# Motor1.net
KiCad netlist of a schematic drawn in Altium Designer
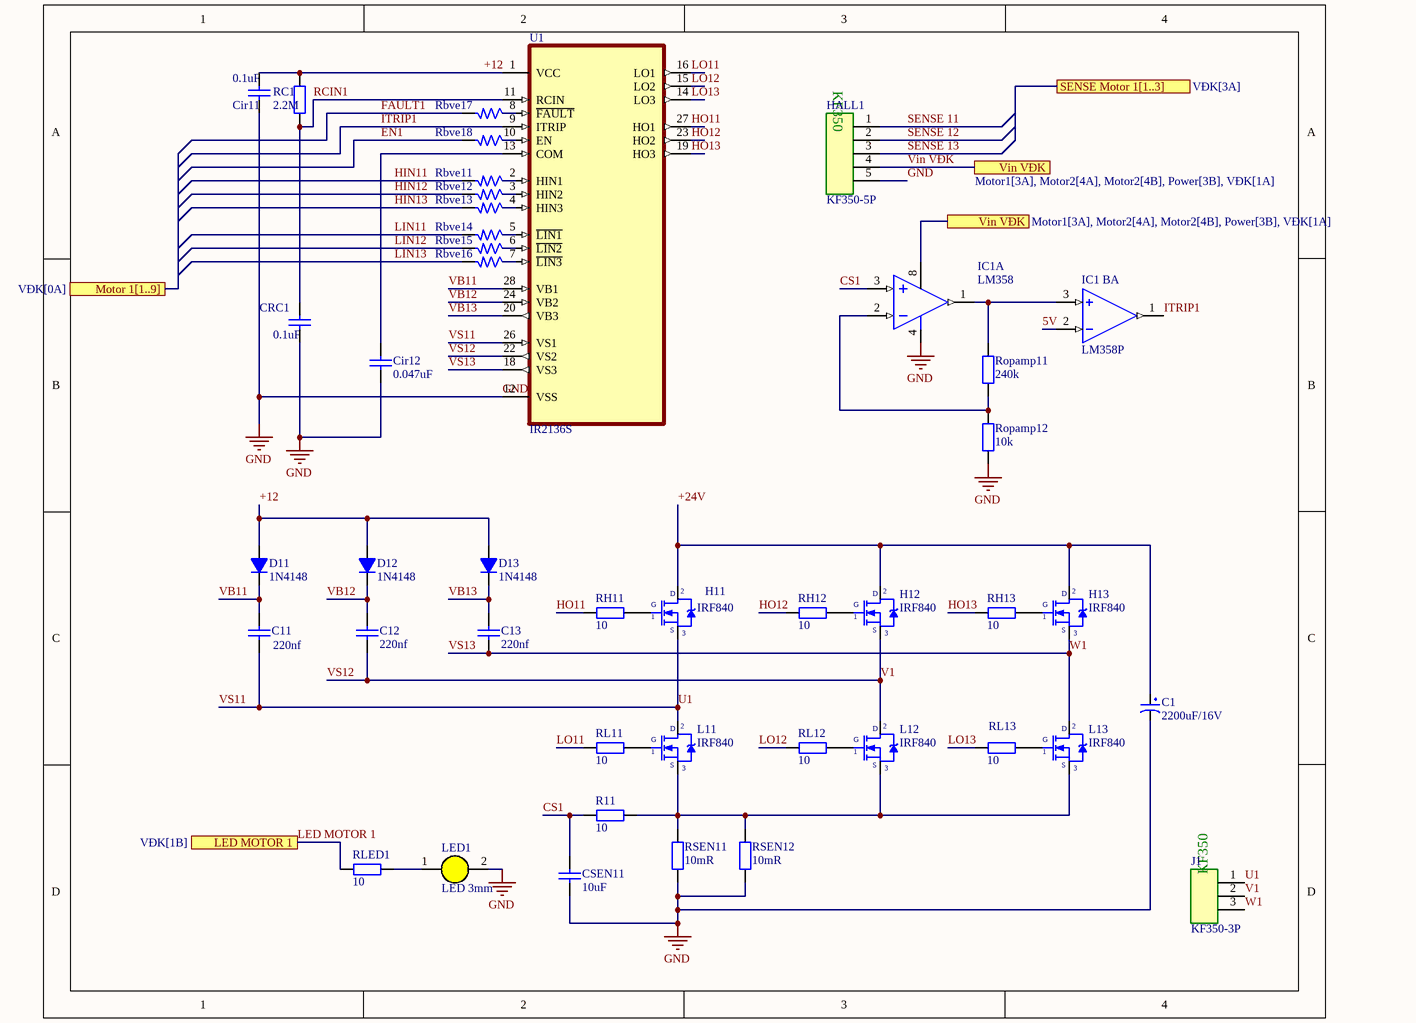
[diagram p0: Motor1.SchDoc]

(export (version "E")
  (design (tool "Eeschema 10.0.6"))
  (components
    (comp (ref "C1")
      (value "2200uF/16V")
      (footprint "CP2/4")
      (description "Cap 2200uF/16V - 1000uF/50V")
      (libsource (lib "SCH_Lib_Devzone") (part "CP5"))
    )
    (comp (ref "C11")
      (value "220nf")
      (footprint "Tu-pico")
      (description "Capacitor")
      (fields (field (name "Comment") "Capacitor Ceramic") (field (name "PUBLISHER") "Altium Limited"))
      (libsource (lib "Devzone_SCHLib") (part "CapCeramic"))
    )
    (comp (ref "C12")
      (value "220nf")
      (footprint "Tu-pico")
      (description "Capacitor")
      (fields (field (name "Comment") "Capacitor Ceramic") (field (name "PUBLISHER") "Altium Limited"))
      (libsource (lib "Devzone_SCHLib") (part "CapCeramic"))
    )
    (comp (ref "C13")
      (value "220nf")
      (footprint "Tu-pico")
      (description "Capacitor")
      (fields (field (name "Comment") "Capacitor Ceramic") (field (name "PUBLISHER") "Altium Limited"))
      (libsource (lib "Devzone_SCHLib") (part "CapCeramic"))
    )
    (comp (ref "Cir11")
      (value "0.1uF")
      (footprint "Tu-pico")
      (description "Capacitor")
      (fields (field (name "Comment") "Capacitor Ceramic") (field (name "PUBLISHER") "Altium Limited"))
      (libsource (lib "Devzone_SCHLib") (part "CapCeramic"))
    )
    (comp (ref "Cir12")
      (value "0.047uF")
      (footprint "Tu-pico")
      (description "Capacitor")
      (fields (field (name "Comment") "Capacitor Ceramic") (field (name "PUBLISHER") "Altium Limited"))
      (libsource (lib "Devzone_SCHLib") (part "CapCeramic"))
    )
    (comp (ref "CRC1")
      (value "0.1uF")
      (footprint "Tu-pico")
      (description "Capacitor")
      (fields (field (name "Comment") "Capacitor Ceramic") (field (name "PUBLISHER") "Altium Limited"))
      (libsource (lib "Devzone_SCHLib") (part "CapCeramic"))
    )
    (comp (ref "CSEN11")
      (value "10uF")
      (footprint "Tu-pico")
      (description "Capacitor")
      (fields (field (name "Comment") "Capacitor Ceramic") (field (name "PUBLISHER") "Altium Limited"))
      (libsource (lib "Devzone_SCHLib") (part "CapCeramic"))
    )
    (comp (ref "D11")
      (value "1N4148")
      (footprint "D0.5A")
      (description "D0.5A")
      (libsource (lib "Devzone_SCHLib") (part "D0.5A"))
    )
    (comp (ref "D12")
      (value "1N4148")
      (footprint "D0.5A")
      (description "D0.5A")
      (libsource (lib "Devzone_SCHLib") (part "D0.5A"))
    )
    (comp (ref "D13")
      (value "1N4148")
      (footprint "D0.5A")
      (description "D0.5A")
      (libsource (lib "Devzone_SCHLib") (part "D0.5A"))
    )
    (comp (ref "H11")
      (value "IRF840")
      (footprint "QTO-220")
      (description "MOSFET N - CHANNEL 500V - 0.75 - 8A - TO-220")
      (libsource (lib "Devzone_SCHLib") (part "IRF840"))
    )
    (comp (ref "H12")
      (value "IRF840")
      (footprint "QTO-220")
      (description "MOSFET N - CHANNEL 500V - 0.75 - 8A - TO-220")
      (libsource (lib "Devzone_SCHLib") (part "IRF840"))
    )
    (comp (ref "H13")
      (value "IRF840")
      (footprint "QTO-220")
      (description "MOSFET N - CHANNEL 500V - 0.75 - 8A - TO-220")
      (libsource (lib "Devzone_SCHLib") (part "IRF840"))
    )
    (comp (ref "HALL1") (value "KF350-5P") (footprint "KF350-5P") (libsource (lib "KF350") (part "KF350-5P")))
    (comp (ref "IC1")
      (value "LM358")
      (footprint "DIP8/W0.3")
      (description "Low-Power Dual Operational Amplifier")
      (libsource (lib "SCH_Lib_Devzone") (part "LM358"))
    )
    (comp (ref "IC1 B")
      (value "LM358P")
      (footprint "DIP794W45P254L959H508Q8")
      (description "Dual, 30-V, 700-kHz operational amplifier")
      (fields (field (name "MF") "Texas Instruments"))
      (libsource (lib "LM358P") (part "LM358P"))
    )
    (comp (ref "J1") (value "KF350-3P") (footprint "KF350-3P") (libsource (lib "KF350") (part "KF350-3P")))
    (comp (ref "L11")
      (value "IRF840")
      (footprint "QTO-220")
      (description "MOSFET N - CHANNEL 500V - 0.75 - 8A - TO-220")
      (libsource (lib "Devzone_SCHLib") (part "IRF840"))
    )
    (comp (ref "L12")
      (value "IRF840")
      (footprint "QTO-220")
      (description "MOSFET N - CHANNEL 500V - 0.75 - 8A - TO-220")
      (libsource (lib "Devzone_SCHLib") (part "IRF840"))
    )
    (comp (ref "L13")
      (value "IRF840")
      (footprint "QTO-220")
      (description "MOSFET N - CHANNEL 500V - 0.75 - 8A - TO-220")
      (libsource (lib "Devzone_SCHLib") (part "IRF840"))
    )
    (comp (ref "LED1")
      (value "LED 3mm")
      (footprint "LED-3MM-YELLOW")
      (description "Cắm")
      (libsource (lib "Altium_Lib_by_KhueNguyenCreator") (part "LED 3mm Vang"))
    )
    (comp (ref "R11")
      (value "10")
      (footprint "R1/4W")
      (description "Resistor 1/4W")
      (libsource (lib "Devzone_SCHLib") (part "R1/4W"))
    )
    (comp (ref "Rbve11")
      (value "1m")
      (footprint "SM-1206")
      (description "Resistor 1/4W")
      (libsource (lib "SCH_Lib_Devzone") (part "R"))
    )
    (comp (ref "Rbve12")
      (value "1m")
      (footprint "SM-1206")
      (description "Resistor 1/4W")
      (libsource (lib "SCH_Lib_Devzone") (part "R"))
    )
    (comp (ref "Rbve13")
      (value "1m")
      (footprint "SM-1206")
      (description "Resistor 1/4W")
      (libsource (lib "SCH_Lib_Devzone") (part "R"))
    )
    (comp (ref "Rbve14")
      (value "1m")
      (footprint "SM-1206")
      (description "Resistor 1/4W")
      (libsource (lib "SCH_Lib_Devzone") (part "R"))
    )
    (comp (ref "Rbve15")
      (value "1m")
      (footprint "SM-1206")
      (description "Resistor 1/4W")
      (libsource (lib "SCH_Lib_Devzone") (part "R"))
    )
    (comp (ref "Rbve16")
      (value "1m")
      (footprint "SM-1206")
      (description "Resistor 1/4W")
      (libsource (lib "SCH_Lib_Devzone") (part "R"))
    )
    (comp (ref "Rbve17")
      (value "1m")
      (footprint "SM-1206")
      (description "Resistor 1/4W")
      (libsource (lib "SCH_Lib_Devzone") (part "R"))
    )
    (comp (ref "Rbve18")
      (value "1m")
      (footprint "SM-1206")
      (description "Resistor 1/4W")
      (libsource (lib "SCH_Lib_Devzone") (part "R"))
    )
    (comp (ref "RC1")
      (value "2.2M")
      (footprint "R1/4W")
      (description "Resistor 1/4W")
      (libsource (lib "Devzone_SCHLib") (part "R1/4W"))
    )
    (comp (ref "RH11")
      (value "10")
      (footprint "R1/4W")
      (description "Resistor 1/4W")
      (libsource (lib "Devzone_SCHLib") (part "R1/4W"))
    )
    (comp (ref "RH12")
      (value "10")
      (footprint "R1/4W")
      (description "Resistor 1/4W")
      (libsource (lib "Devzone_SCHLib") (part "R1/4W"))
    )
    (comp (ref "RH13")
      (value "10")
      (footprint "R1/4W")
      (description "Resistor 1/4W")
      (libsource (lib "Devzone_SCHLib") (part "R1/4W"))
    )
    (comp (ref "RL11")
      (value "10")
      (footprint "R1/4W")
      (description "Resistor 1/4W")
      (libsource (lib "Devzone_SCHLib") (part "R1/4W"))
    )
    (comp (ref "RL12")
      (value "10")
      (footprint "R1/4W")
      (description "Resistor 1/4W")
      (libsource (lib "Devzone_SCHLib") (part "R1/4W"))
    )
    (comp (ref "RL13")
      (value "10")
      (footprint "R1/4W")
      (description "Resistor 1/4W")
      (libsource (lib "Devzone_SCHLib") (part "R1/4W"))
    )
    (comp (ref "RLED1")
      (value "10")
      (footprint "R1/4W")
      (description "Resistor 1/4W")
      (libsource (lib "Devzone_SCHLib") (part "R1/4W"))
    )
    (comp (ref "Ropamp11")
      (value "240k")
      (footprint "R1/4W")
      (description "Resistor 1/4W")
      (libsource (lib "Devzone_SCHLib") (part "R1/4W"))
    )
    (comp (ref "Ropamp12")
      (value "10k")
      (footprint "R1/4W")
      (description "Resistor 1/4W")
      (libsource (lib "Devzone_SCHLib") (part "R1/4W"))
    )
    (comp (ref "RSEN11")
      (value "10mR")
      (footprint "Shunt 10mR 1.2x10x7MM")
      (description "Shunt 10mR 1.2x10x7MM")
      (libsource (lib "SCH_Lib_Devzone") (part "Shunt 10mR 1.2x10x7MM"))
    )
    (comp (ref "RSEN12")
      (value "10mR")
      (footprint "Shunt 10mR 1.2x10x7MM")
      (description "Shunt 10mR 1.2x10x7MM")
      (libsource (lib "SCH_Lib_Devzone") (part "Shunt 10mR 1.2x10x7MM"))
    )
    (comp (ref "U1")
      (value "IR2136S")
      (footprint "SOIC127PX1032X265-28N")
      (description "IC Ä‘iá»u khiá»ƒn ná»­a cáº§u cá»•ng Ä‘áº£o ngÆ°á»£c 28-SOIC")
      (fields (field (name "MF") "Infineon"))
      (libsource (lib "IR2136S") (part "IR2136S"))
    )
  )
  (nets
    (net (code "1") (name "/+12") (class "Default")
      (node (ref "Cir11") (pin "1") (pinfunction "1_1") (pintype "passive"))
      (node (ref "D11") (pin "1") (pinfunction "A_1") (pintype "passive"))
      (node (ref "D12") (pin "1") (pinfunction "A_1") (pintype "passive"))
      (node (ref "D13") (pin "1") (pinfunction "A_1") (pintype "passive"))
      (node (ref "RC1") (pin "2") (pinfunction "2_2") (pintype "passive"))
      (node (ref "U1") (pin "1") (pinfunction "VCC_1") (pintype "power_in"))
    )
    (net (code "2") (name "/+24V") (class "Default")
      (node (ref "C1") (pin "1") (pinfunction "1_1") (pintype "passive"))
      (node (ref "H11") (pin "2") (pinfunction "D_2") (pintype "passive"))
      (node (ref "H12") (pin "2") (pinfunction "D_2") (pintype "passive"))
      (node (ref "H13") (pin "2") (pinfunction "D_2") (pintype "passive"))
    )
    (net (code "3") (name "/5V") (class "Default")
      (node (ref "IC1 B") (pin "2") (pinfunction "-IN1_2") (pintype "input"))
    )
    (net (code "4") (name "/CS1") (class "Default")
      (node (ref "CSEN11") (pin "1") (pinfunction "1_1") (pintype "passive"))
      (node (ref "IC1") (pin "3") (pinfunction "IN+_3") (pintype "input"))
      (node (ref "R11") (pin "2") (pinfunction "2_2") (pintype "passive"))
    )
    (net (code "5") (name "/EN1") (class "Default")
      (node (ref "Rbve18") (pin "2") (pinfunction "2_2") (pintype "passive"))
    )
    (net (code "6") (name "/FAULT1") (class "Default")
      (node (ref "Rbve17") (pin "2") (pinfunction "2_2") (pintype "passive"))
    )
    (net (code "7") (name "/HIN11") (class "Default")
      (node (ref "Rbve11") (pin "2") (pinfunction "2_2") (pintype "passive"))
    )
    (net (code "8") (name "/HIN12") (class "Default")
      (node (ref "Rbve12") (pin "2") (pinfunction "2_2") (pintype "passive"))
    )
    (net (code "9") (name "/HIN13") (class "Default")
      (node (ref "Rbve13") (pin "2") (pinfunction "2_2") (pintype "passive"))
    )
    (net (code "10") (name "/HO11") (class "Default")
      (node (ref "RH11") (pin "1") (pinfunction "1_1") (pintype "passive"))
      (node (ref "U1") (pin "27") (pinfunction "HO1_27") (pintype "output"))
    )
    (net (code "11") (name "/HO12") (class "Default")
      (node (ref "RH12") (pin "1") (pinfunction "1_1") (pintype "passive"))
      (node (ref "U1") (pin "23") (pinfunction "HO2_23") (pintype "output"))
    )
    (net (code "12") (name "/HO13") (class "Default")
      (node (ref "RH13") (pin "1") (pinfunction "1_1") (pintype "passive"))
      (node (ref "U1") (pin "19") (pinfunction "HO3_19") (pintype "output"))
    )
    (net (code "13") (name "/ITRIP1") (class "Default")
      (node (ref "IC1 B") (pin "1") (pinfunction "OUT1_1") (pintype "output"))
      (node (ref "U1") (pin "9") (pinfunction "ITRIP_9") (pintype "input"))
    )
    (net (code "14") (name "/LED MOTOR 1") (class "Default")
      (node (ref "RLED1") (pin "2") (pinfunction "2_2") (pintype "passive"))
    )
    (net (code "15") (name "/LIN11") (class "Default")
      (node (ref "Rbve14") (pin "2") (pinfunction "2_2") (pintype "passive"))
    )
    (net (code "16") (name "/LIN12") (class "Default")
      (node (ref "Rbve15") (pin "2") (pinfunction "2_2") (pintype "passive"))
    )
    (net (code "17") (name "/LIN13") (class "Default")
      (node (ref "Rbve16") (pin "2") (pinfunction "2_2") (pintype "passive"))
    )
    (net (code "18") (name "/LO11") (class "Default")
      (node (ref "RL11") (pin "1") (pinfunction "1_1") (pintype "passive"))
      (node (ref "U1") (pin "16") (pinfunction "LO1_16") (pintype "output"))
    )
    (net (code "19") (name "/LO12") (class "Default")
      (node (ref "RL12") (pin "1") (pinfunction "1_1") (pintype "passive"))
      (node (ref "U1") (pin "15") (pinfunction "LO2_15") (pintype "output"))
    )
    (net (code "20") (name "/LO13") (class "Default")
      (node (ref "RL13") (pin "2") (pinfunction "2_2") (pintype "passive"))
      (node (ref "U1") (pin "14") (pinfunction "LO3_14") (pintype "output"))
    )
    (net (code "22") (name "/RCIN1") (class "Default")
      (node (ref "CRC1") (pin "1") (pinfunction "1_1") (pintype "passive"))
      (node (ref "RC1") (pin "1") (pinfunction "1_1") (pintype "passive"))
      (node (ref "U1") (pin "11") (pinfunction "RCIN_11") (pintype "input"))
    )
    (net (code "23") (name "/SENSE 11") (class "Default")
      (node (ref "HALL1") (pin "1") (pinfunction "1_1") (pintype "passive"))
    )
    (net (code "24") (name "/SENSE 12") (class "Default")
      (node (ref "HALL1") (pin "2") (pinfunction "2_2") (pintype "passive"))
    )
    (net (code "25") (name "/SENSE 13") (class "Default")
      (node (ref "HALL1") (pin "3") (pinfunction "3_3") (pintype "passive"))
    )
    (net (code "27") (name "/U1") (class "Default")
      (node (ref "C11") (pin "2") (pinfunction "2_2") (pintype "passive"))
      (node (ref "H11") (pin "3") (pinfunction "S_3") (pintype "passive"))
      (node (ref "J1") (pin "1") (pinfunction "1_1") (pintype "passive"))
      (node (ref "L11") (pin "2") (pinfunction "D_2") (pintype "passive"))
      (node (ref "U1") (pin "26") (pinfunction "VS1_26") (pintype "input"))
    )
    (net (code "28") (name "/V1") (class "Default")
      (node (ref "C12") (pin "2") (pinfunction "2_2") (pintype "passive"))
      (node (ref "H12") (pin "3") (pinfunction "S_3") (pintype "passive"))
      (node (ref "J1") (pin "2") (pinfunction "2_2") (pintype "passive"))
      (node (ref "L12") (pin "2") (pinfunction "D_2") (pintype "passive"))
      (node (ref "U1") (pin "22") (pinfunction "VS2_22") (pintype "output"))
    )
    (net (code "29") (name "/VB11") (class "Default")
      (node (ref "C11") (pin "1") (pinfunction "1_1") (pintype "passive"))
      (node (ref "D11") (pin "2") (pinfunction "K_2") (pintype "passive"))
      (node (ref "U1") (pin "28") (pinfunction "VB1_28") (pintype "input"))
    )
    (net (code "30") (name "/VB12") (class "Default")
      (node (ref "C12") (pin "1") (pinfunction "1_1") (pintype "passive"))
      (node (ref "D12") (pin "2") (pinfunction "K_2") (pintype "passive"))
      (node (ref "U1") (pin "24") (pinfunction "VB2_24") (pintype "input"))
    )
    (net (code "31") (name "/VB13") (class "Default")
      (node (ref "C13") (pin "1") (pinfunction "1_1") (pintype "passive"))
      (node (ref "D13") (pin "2") (pinfunction "K_2") (pintype "passive"))
      (node (ref "U1") (pin "20") (pinfunction "VB3_20") (pintype "output"))
    )
    (net (code "32") (name "/VS13") (class "Default")
      (node (ref "C13") (pin "2") (pinfunction "2_2") (pintype "passive"))
      (node (ref "H13") (pin "3") (pinfunction "S_3") (pintype "passive"))
      (node (ref "J1") (pin "3") (pinfunction "3_3") (pintype "passive"))
      (node (ref "L13") (pin "2") (pinfunction "D_2") (pintype "passive"))
      (node (ref "U1") (pin "18") (pinfunction "VS3_18") (pintype "output"))
    )
    (net (code "33") (name "/Vin VĐK") (class "Default")
      (node (ref "HALL1") (pin "4") (pinfunction "4_4") (pintype "passive"))
      (node (ref "IC1") (pin "8") (pinfunction "+V_8") (pintype "passive"))
    )
    (net (code "34") (name "GND") (class "Default")
      (node (ref "C1") (pin "2") (pinfunction "2_2") (pintype "passive"))
      (node (ref "CRC1") (pin "2") (pinfunction "2_2") (pintype "passive"))
      (node (ref "CSEN11") (pin "2") (pinfunction "2_2") (pintype "passive"))
      (node (ref "Cir11") (pin "2") (pinfunction "2_2") (pintype "passive"))
      (node (ref "Cir12") (pin "2") (pinfunction "2_2") (pintype "passive"))
      (node (ref "HALL1") (pin "5") (pinfunction "5_5") (pintype "passive"))
      (node (ref "IC1") (pin "4") (pinfunction "-V_4") (pintype "passive"))
      (node (ref "LED1") (pin "2") (pinfunction "K_2") (pintype "passive"))
      (node (ref "RSEN11") (pin "1") (pinfunction "1_1") (pintype "passive"))
      (node (ref "RSEN12") (pin "1") (pinfunction "1_1") (pintype "passive"))
      (node (ref "Ropamp12") (pin "2") (pinfunction "2_2") (pintype "passive"))
      (node (ref "U1") (pin "12") (pinfunction "VSS_12") (pintype "passive"))
    )
    (net (code "35") (name "Net-(H11-G)") (class "Default")
      (node (ref "H11") (pin "1") (pinfunction "G_1") (pintype "passive"))
      (node (ref "RH11") (pin "2") (pinfunction "2_2") (pintype "passive"))
    )
    (net (code "36") (name "Net-(H12-G)") (class "Default")
      (node (ref "H12") (pin "1") (pinfunction "G_1") (pintype "passive"))
      (node (ref "RH12") (pin "2") (pinfunction "2_2") (pintype "passive"))
    )
    (net (code "37") (name "Net-(H13-G)") (class "Default")
      (node (ref "H13") (pin "1") (pinfunction "G_1") (pintype "passive"))
      (node (ref "RH13") (pin "2") (pinfunction "2_2") (pintype "passive"))
    )
    (net (code "38") (name "Net-(IC1 BA-+IN1)") (class "Default")
      (node (ref "IC1") (pin "1") (pinfunction "OUT_1") (pintype "output"))
      (node (ref "IC1 B") (pin "3") (pinfunction "+IN1_3") (pintype "input"))
      (node (ref "Ropamp11") (pin "1") (pinfunction "1_1") (pintype "passive"))
    )
    (net (code "39") (name "Net-(IC1A-IN-)") (class "Default")
      (node (ref "IC1") (pin "2") (pinfunction "IN-_2") (pintype "input"))
      (node (ref "Ropamp11") (pin "2") (pinfunction "2_2") (pintype "passive"))
      (node (ref "Ropamp12") (pin "1") (pinfunction "1_1") (pintype "passive"))
    )
    (net (code "40") (name "Net-(L11-G)") (class "Default")
      (node (ref "L11") (pin "1") (pinfunction "G_1") (pintype "passive"))
      (node (ref "RL11") (pin "2") (pinfunction "2_2") (pintype "passive"))
    )
    (net (code "41") (name "Net-(L11-S)") (class "Default")
      (node (ref "L11") (pin "3") (pinfunction "S_3") (pintype "passive"))
      (node (ref "L12") (pin "3") (pinfunction "S_3") (pintype "passive"))
      (node (ref "L13") (pin "3") (pinfunction "S_3") (pintype "passive"))
      (node (ref "R11") (pin "1") (pinfunction "1_1") (pintype "passive"))
      (node (ref "RSEN11") (pin "2") (pinfunction "2_2") (pintype "passive"))
      (node (ref "RSEN12") (pin "2") (pinfunction "2_2") (pintype "passive"))
    )
    (net (code "42") (name "Net-(L12-G)") (class "Default")
      (node (ref "L12") (pin "1") (pinfunction "G_1") (pintype "passive"))
      (node (ref "RL12") (pin "2") (pinfunction "2_2") (pintype "passive"))
    )
    (net (code "43") (name "Net-(L13-G)") (class "Default")
      (node (ref "L13") (pin "1") (pinfunction "G_1") (pintype "passive"))
      (node (ref "RL13") (pin "1") (pinfunction "1_1") (pintype "passive"))
    )
    (net (code "44") (name "Net-(LED1-A)") (class "Default")
      (node (ref "LED1") (pin "1") (pinfunction "A_1") (pintype "passive"))
      (node (ref "RLED1") (pin "1") (pinfunction "1_1") (pintype "passive"))
    )
    (net (code "45") (name "Net-(U1-COM)") (class "Default")
      (node (ref "Cir12") (pin "1") (pinfunction "1_1") (pintype "passive"))
      (node (ref "U1") (pin "13") (pinfunction "COM_13") (pintype "input"))
    )
    (net (code "46") (name "Net-(U1-EN)") (class "Default")
      (node (ref "Rbve18") (pin "1") (pinfunction "1_1") (pintype "passive"))
      (node (ref "U1") (pin "10") (pinfunction "EN_10") (pintype "input"))
    )
    (net (code "47") (name "Net-(U1-HIN1)") (class "Default")
      (node (ref "Rbve11") (pin "1") (pinfunction "1_1") (pintype "passive"))
      (node (ref "U1") (pin "2") (pinfunction "HIN1_2") (pintype "input"))
    )
    (net (code "48") (name "Net-(U1-HIN2)") (class "Default")
      (node (ref "Rbve12") (pin "1") (pinfunction "1_1") (pintype "passive"))
      (node (ref "U1") (pin "3") (pinfunction "HIN2_3") (pintype "input"))
    )
    (net (code "49") (name "Net-(U1-HIN3)") (class "Default")
      (node (ref "Rbve13") (pin "1") (pinfunction "1_1") (pintype "passive"))
      (node (ref "U1") (pin "4") (pinfunction "HIN3_4") (pintype "input"))
    )
    (net (code "50") (name "Net-(U1-~{FAULT})") (class "Default")
      (node (ref "Rbve17") (pin "1") (pinfunction "1_1") (pintype "passive"))
      (node (ref "U1") (pin "8") (pinfunction "~{FAULT}_8") (pintype "input"))
    )
    (net (code "51") (name "Net-(U1-~{LIN1})") (class "Default")
      (node (ref "Rbve14") (pin "1") (pinfunction "1_1") (pintype "passive"))
      (node (ref "U1") (pin "5") (pinfunction "~{LIN1}_5") (pintype "input"))
    )
    (net (code "52") (name "Net-(U1-~{LIN2})") (class "Default")
      (node (ref "Rbve15") (pin "1") (pinfunction "1_1") (pintype "passive"))
      (node (ref "U1") (pin "6") (pinfunction "~{LIN2}_6") (pintype "input"))
    )
    (net (code "53") (name "Net-(U1-~{LIN3})") (class "Default")
      (node (ref "Rbve16") (pin "1") (pinfunction "1_1") (pintype "passive"))
      (node (ref "U1") (pin "7") (pinfunction "~{LIN3}_7") (pintype "input"))
    )
  )
)
